# TankWaterLevelSensorV2_3.net
KiCad netlist of a schematic drawn in EAGLE
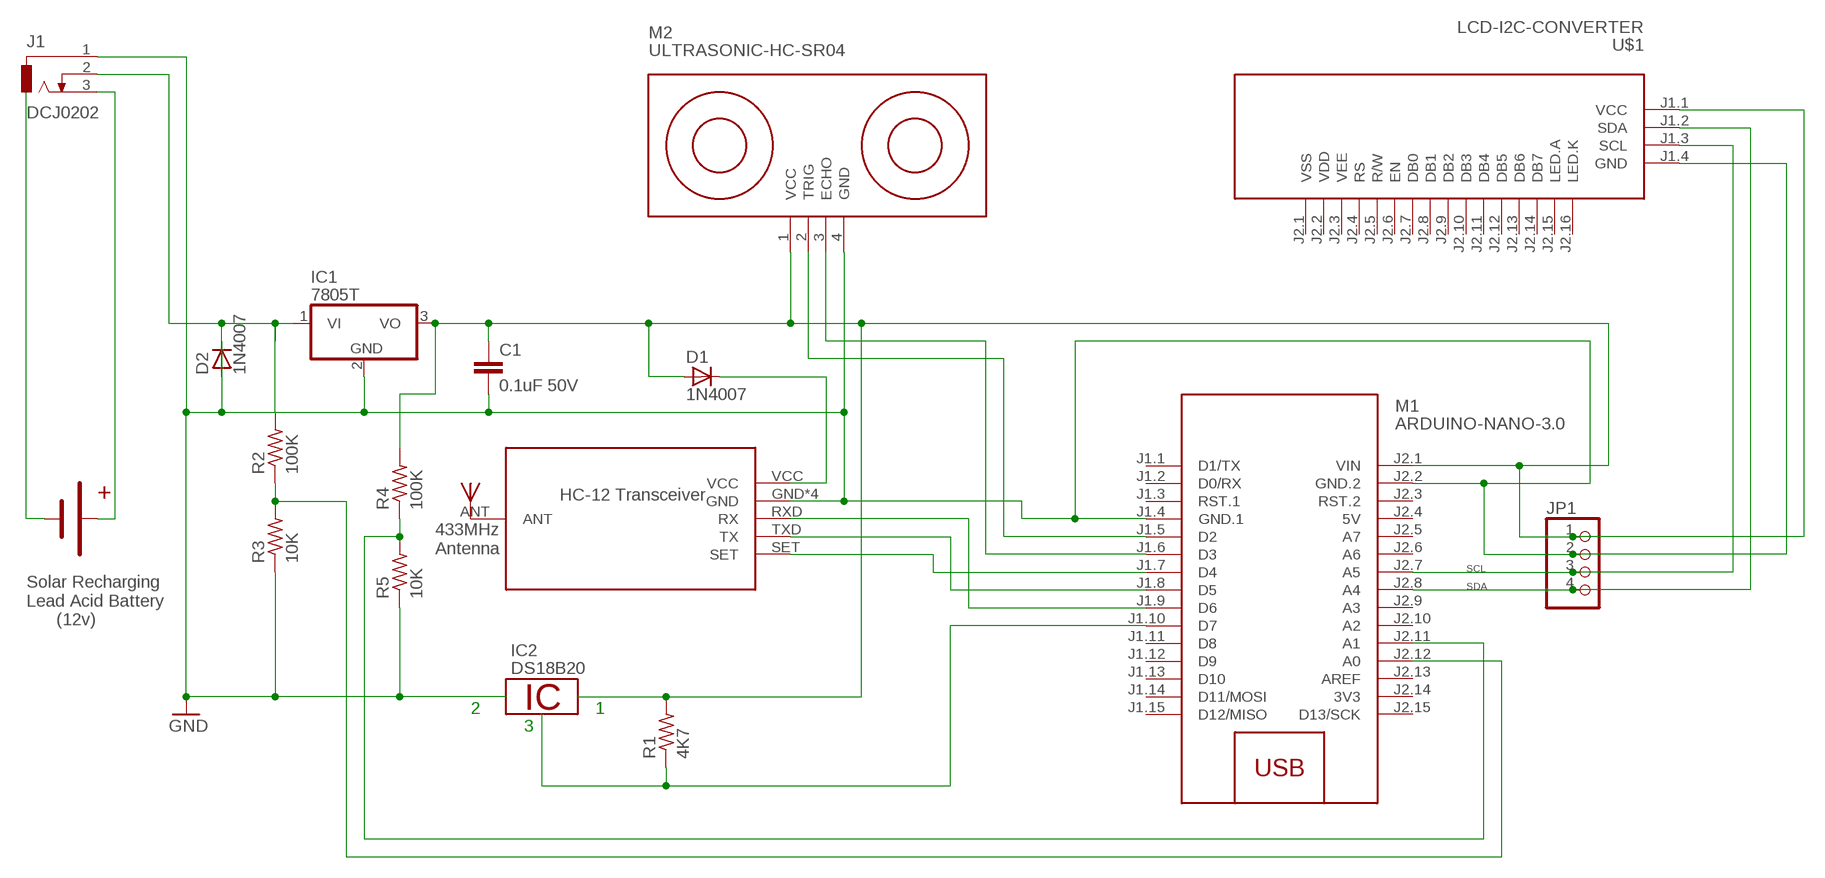
[diagram p0: schematic, sheet 1]

(export (version "E")
  (design (tool "Eeschema 10.0.6"))
  (components
    (comp (ref "433MHZ_ANT")
      (value "ANTENNA")
      (footprint "eagle-import:ANTENNA")
      (libsource (lib "eagle-import") (part "ANTENNA"))
    )
    (comp (ref "C1")
      (value "0.1uF 50V")
      (footprint "eagle-import:C5B2.5")
      (libsource (lib "eagle-import") (part "C5/2.5"))
    )
    (comp (ref "D1")
      (value "1N4007")
      (footprint "eagle-import:SMA")
      (libsource (lib "eagle-import") (part "1N4007"))
    )
    (comp (ref "D2")
      (value "1N4007")
      (footprint "eagle-import:SMA")
      (libsource (lib "eagle-import") (part "1N4007"))
    )
    (comp (ref "IC1")
      (value "7805T")
      (footprint "eagle-import:TO220H")
      (fields (field (name "SPICEPREFIX") "J"))
      (libsource (lib "eagle-import") (part "78T05"))
    )
    (comp (ref "IC2")
      (value "DS18B20")
      (footprint "eagle-import:TO92-")
      (libsource (lib "eagle-import") (part "DS18B20"))
    )
    (comp (ref "J1")
      (value "DCJ0202")
      (footprint "eagle-import:DCJ0202")
      (libsource (lib "eagle-import") (part "DCJ0202"))
    )
    (comp (ref "JP1")
      (value "PINHD-1X4/LONG")
      (footprint "eagle-import:1X04")
      (libsource (lib "eagle-import") (part "PINHD-1X4/LONG"))
    )
    (comp (ref "M1")
      (value "ARDUINO-NANO-3.0")
      (footprint "eagle-import:ARDUINO-NANO-3.0")
      (libsource (lib "eagle-import") (part "ARDUINO-NANO-3.0"))
    )
    (comp (ref "M2")
      (value "ULTRASONIC-HC-SR04")
      (footprint "eagle-import:ULTRASONIC-HC-SR04")
      (libsource (lib "eagle-import") (part "ULTRASONIC-HC-SR04"))
    )
    (comp (ref "M3")
      (value "HC-12_FOOTPRINT")
      (footprint "eagle-import:HC-12_FOOTPRINT")
      (libsource (lib "eagle-import") (part "HC-12_FOOTPRINT"))
    )
    (comp (ref "R1")
      (value "4K7")
      (footprint "eagle-import:0204V")
      (libsource (lib "eagle-import") (part "R-US_0204/2V"))
    )
    (comp (ref "R2")
      (value "100K")
      (footprint "eagle-import:0204V")
      (libsource (lib "eagle-import") (part "R-US_0204/2V"))
    )
    (comp (ref "R3")
      (value "10K")
      (footprint "eagle-import:0204V")
      (libsource (lib "eagle-import") (part "R-US_0204/2V"))
    )
    (comp (ref "R4")
      (value "100K")
      (footprint "eagle-import:0204V")
      (libsource (lib "eagle-import") (part "R-US_0204/2V"))
    )
    (comp (ref "R5")
      (value "10K")
      (footprint "eagle-import:0204V")
      (libsource (lib "eagle-import") (part "R-US_0204/2V"))
    )
    (comp (ref "SOLAR_BATTERY_12V")
      (value "12v")
      (footprint "eagle-import:BATTERYPAD")
      (libsource (lib "eagle-import") (part "BATTERYPAD"))
    )
    (comp (ref "U$1")
      (value "LCD-I2C-CONVERTER")
      (footprint "eagle-import:LCD-I2C-CONVERTER")
      (libsource (lib "eagle-import") (part "LCD-I2C-CONVERTER"))
    )
  )
  (nets
    (net (code "1") (name "/3V3") (class "Default")
      (node (ref "M1") (pin "J2.14") (pinfunction "3V3_J2.14") (pintype "power_in"))
    )
    (net (code "2") (name "/5V") (class "Default")
      (node (ref "M1") (pin "J2.4") (pinfunction "5V_J2.4") (pintype "power_in"))
    )
    (net (code "3") (name "GND") (class "Default")
      (node (ref "C1") (pin "2") (pinfunction "2_2") (pintype "passive"))
      (node (ref "D2") (pin "A") (pinfunction "A_A") (pintype "passive"))
      (node (ref "D2") (pin "K") (pinfunction "C_K") (pintype "passive"))
      (node (ref "IC1") (pin "1") (pinfunction "VI_1") (pintype "input"))
      (node (ref "IC1") (pin "2") (pinfunction "GND_2") (pintype "passive"))
      (node (ref "J1") (pin "1") (pinfunction "1_1") (pintype "passive"))
      (node (ref "J1") (pin "2") (pinfunction "2_2") (pintype "passive"))
      (node (ref "JP1") (pin "2") (pinfunction "2_2") (pintype "passive"))
      (node (ref "M1") (pin "J1.4") (pinfunction "GND.1_J1.4") (pintype "power_in"))
      (node (ref "M1") (pin "J2.2") (pinfunction "GND.2_J2.2") (pintype "power_in"))
      (node (ref "M2") (pin "4") (pinfunction "GND_4") (pintype "power_in"))
      (node (ref "M3") (pin "GND") (pinfunction "GND_GND") (pintype "bidirectional"))
      (node (ref "M3") (pin "GND1") (pinfunction "GND_GND1") (pintype "bidirectional"))
      (node (ref "M3") (pin "GND2") (pinfunction "GND_GND2") (pintype "bidirectional"))
      (node (ref "M3") (pin "MCHFIX") (pinfunction "GND_MCHFIX") (pintype "bidirectional"))
      (node (ref "R2") (pin "2") (pinfunction "2_2") (pintype "passive"))
      (node (ref "R3") (pin "1") (pinfunction "1_1") (pintype "passive"))
      (node (ref "R5") (pin "1") (pinfunction "1_1") (pintype "passive"))
      (node (ref "U$1") (pin "J1.4") (pinfunction "GND_J1.4") (pintype "power_in"))
    )
    (net (code "4") (name "Net-(433MHZ_ANT-PadANT)") (class "Default")
      (node (ref "433MHZ_ANT") (pin "ANT") (pinfunction "ANT_ANT") (pintype "bidirectional"))
      (node (ref "M3") (pin "ANT") (pinfunction "ANT_ANT") (pintype "bidirectional"))
    )
    (net (code "5") (name "Net-(D1-C)") (class "Default")
      (node (ref "D1") (pin "K") (pinfunction "C_K") (pintype "passive"))
      (node (ref "M3") (pin "VCC") (pinfunction "VCC_VCC") (pintype "bidirectional"))
    )
    (net (code "6") (name "Net-(IC1-VO)") (class "Default")
      (node (ref "C1") (pin "1") (pinfunction "1_1") (pintype "passive"))
      (node (ref "D1") (pin "A") (pinfunction "A_A") (pintype "passive"))
      (node (ref "IC1") (pin "3") (pinfunction "VO_3") (pintype "passive"))
      (node (ref "JP1") (pin "1") (pinfunction "1_1") (pintype "passive"))
      (node (ref "M1") (pin "J2.1") (pinfunction "VIN_J2.1") (pintype "power_in"))
      (node (ref "M2") (pin "1") (pinfunction "VCC_1") (pintype "power_in"))
      (node (ref "R1") (pin "2") (pinfunction "2_2") (pintype "passive"))
      (node (ref "R4") (pin "2") (pinfunction "2_2") (pintype "passive"))
      (node (ref "U$1") (pin "J1.1") (pinfunction "VCC_J1.1") (pintype "power_in"))
    )
    (net (code "7") (name "Net-(J1-Pad3)") (class "Default")
      (node (ref "J1") (pin "3") (pinfunction "3_3") (pintype "passive"))
      (node (ref "SOLAR_BATTERY_12V") (pin "+VE") (pinfunction "+VE_+VE") (pintype "power_in"))
    )
    (net (code "8") (name "Net-(M1-A0)") (class "Default")
      (node (ref "M1") (pin "J2.12") (pinfunction "A0_J2.12") (pintype "bidirectional"))
      (node (ref "R2") (pin "1") (pinfunction "1_1") (pintype "passive"))
      (node (ref "R3") (pin "2") (pinfunction "2_2") (pintype "passive"))
    )
    (net (code "9") (name "Net-(M1-A1)") (class "Default")
      (node (ref "M1") (pin "J2.11") (pinfunction "A1_J2.11") (pintype "bidirectional"))
      (node (ref "R4") (pin "1") (pinfunction "1_1") (pintype "passive"))
      (node (ref "R5") (pin "2") (pinfunction "2_2") (pintype "passive"))
    )
    (net (code "10") (name "Net-(M1-A4)") (class "Default")
      (node (ref "JP1") (pin "4") (pinfunction "4_4") (pintype "passive"))
      (node (ref "M1") (pin "J2.8") (pinfunction "A4_J2.8") (pintype "bidirectional"))
      (node (ref "U$1") (pin "J1.2") (pinfunction "SDA_J1.2") (pintype "bidirectional"))
    )
    (net (code "11") (name "Net-(M1-A5)") (class "Default")
      (node (ref "JP1") (pin "3") (pinfunction "3_3") (pintype "passive"))
      (node (ref "M1") (pin "J2.7") (pinfunction "A5_J2.7") (pintype "bidirectional"))
      (node (ref "U$1") (pin "J1.3") (pinfunction "SCL_J1.3") (pintype "bidirectional"))
    )
    (net (code "12") (name "Net-(M1-D2)") (class "Default")
      (node (ref "M1") (pin "J1.5") (pinfunction "D2_J1.5") (pintype "bidirectional"))
      (node (ref "M2") (pin "2") (pinfunction "TRIG_2") (pintype "input"))
    )
    (net (code "13") (name "Net-(M1-D3)") (class "Default")
      (node (ref "M1") (pin "J1.6") (pinfunction "D3_J1.6") (pintype "bidirectional"))
      (node (ref "M2") (pin "3") (pinfunction "ECHO_3") (pintype "output"))
    )
    (net (code "14") (name "Net-(M1-D4)") (class "Default")
      (node (ref "M1") (pin "J1.7") (pinfunction "D4_J1.7") (pintype "bidirectional"))
      (node (ref "M3") (pin "SET") (pinfunction "SET_SET") (pintype "bidirectional"))
    )
    (net (code "15") (name "Net-(M1-D5)") (class "Default")
      (node (ref "M1") (pin "J1.8") (pinfunction "D5_J1.8") (pintype "bidirectional"))
      (node (ref "M3") (pin "TXD") (pinfunction "TX_TXD") (pintype "bidirectional"))
    )
    (net (code "16") (name "Net-(M1-D6)") (class "Default")
      (node (ref "M1") (pin "J1.9") (pinfunction "D6_J1.9") (pintype "bidirectional"))
      (node (ref "M3") (pin "RXD") (pinfunction "RX_RXD") (pintype "bidirectional"))
    )
    (net (code "17") (name "Net-(M1-D7)") (class "Default")
      (node (ref "M1") (pin "J1.10") (pinfunction "D7_J1.10") (pintype "bidirectional"))
      (node (ref "R1") (pin "1") (pinfunction "1_1") (pintype "passive"))
    )
    (net (code "18") (name "unconnected-(M1-A2-PadJ2.10)") (class "Default")
      (node (ref "M1") (pin "J2.10") (pinfunction "A2_J2.10") (pintype "bidirectional"))
    )
    (net (code "19") (name "unconnected-(M1-A3-PadJ2.9)") (class "Default")
      (node (ref "M1") (pin "J2.9") (pinfunction "A3_J2.9") (pintype "bidirectional"))
    )
    (net (code "20") (name "unconnected-(M1-A6-PadJ2.6)") (class "Default")
      (node (ref "M1") (pin "J2.6") (pinfunction "A6_J2.6") (pintype "bidirectional"))
    )
    (net (code "21") (name "unconnected-(M1-A7-PadJ2.5)") (class "Default")
      (node (ref "M1") (pin "J2.5") (pinfunction "A7_J2.5") (pintype "bidirectional"))
    )
    (net (code "22") (name "unconnected-(M1-AREF-PadJ2.13)") (class "Default")
      (node (ref "M1") (pin "J2.13") (pinfunction "AREF_J2.13") (pintype "bidirectional"))
    )
    (net (code "23") (name "unconnected-(M1-D0{slash}RX-PadJ1.2)") (class "Default")
      (node (ref "M1") (pin "J1.2") (pinfunction "D0/RX_J1.2") (pintype "bidirectional"))
    )
    (net (code "24") (name "unconnected-(M1-D1{slash}TX-PadJ1.1)") (class "Default")
      (node (ref "M1") (pin "J1.1") (pinfunction "D1/TX_J1.1") (pintype "bidirectional"))
    )
    (net (code "25") (name "unconnected-(M1-D8-PadJ1.11)") (class "Default")
      (node (ref "M1") (pin "J1.11") (pinfunction "D8_J1.11") (pintype "bidirectional"))
    )
    (net (code "26") (name "unconnected-(M1-D9-PadJ1.12)") (class "Default")
      (node (ref "M1") (pin "J1.12") (pinfunction "D9_J1.12") (pintype "bidirectional"))
    )
    (net (code "27") (name "unconnected-(M1-D10-PadJ1.13)") (class "Default")
      (node (ref "M1") (pin "J1.13") (pinfunction "D10_J1.13") (pintype "bidirectional"))
    )
    (net (code "28") (name "unconnected-(M1-D11{slash}MOSI-PadJ1.14)") (class "Default")
      (node (ref "M1") (pin "J1.14") (pinfunction "D11/MOSI_J1.14") (pintype "bidirectional"))
    )
    (net (code "29") (name "unconnected-(M1-D12{slash}MISO-PadJ1.15)") (class "Default")
      (node (ref "M1") (pin "J1.15") (pinfunction "D12/MISO_J1.15") (pintype "bidirectional"))
    )
    (net (code "30") (name "unconnected-(M1-D13{slash}SCK-PadJ2.15)") (class "Default")
      (node (ref "M1") (pin "J2.15") (pinfunction "D13/SCK_J2.15") (pintype "bidirectional"))
    )
    (net (code "31") (name "unconnected-(M1-RST.1-PadJ1.3)") (class "Default")
      (node (ref "M1") (pin "J1.3") (pinfunction "RST.1_J1.3") (pintype "bidirectional"))
    )
    (net (code "32") (name "unconnected-(M1-RST.2-PadJ2.3)") (class "Default")
      (node (ref "M1") (pin "J2.3") (pinfunction "RST.2_J2.3") (pintype "bidirectional"))
    )
    (net (code "33") (name "unconnected-(SOLAR_BATTERY_12V-Pad-VE)") (class "Default")
      (node (ref "SOLAR_BATTERY_12V") (pin "-VE") (pinfunction "-VE_-VE") (pintype "power_in"))
    )
    (net (code "34") (name "unconnected-(U$1-DB0-PadJ2.7)") (class "Default")
      (node (ref "U$1") (pin "J2.7") (pinfunction "DB0_J2.7") (pintype "bidirectional"))
    )
    (net (code "35") (name "unconnected-(U$1-DB1-PadJ2.8)") (class "Default")
      (node (ref "U$1") (pin "J2.8") (pinfunction "DB1_J2.8") (pintype "bidirectional"))
    )
    (net (code "36") (name "unconnected-(U$1-DB2-PadJ2.9)") (class "Default")
      (node (ref "U$1") (pin "J2.9") (pinfunction "DB2_J2.9") (pintype "bidirectional"))
    )
    (net (code "37") (name "unconnected-(U$1-DB3-PadJ2.10)") (class "Default")
      (node (ref "U$1") (pin "J2.10") (pinfunction "DB3_J2.10") (pintype "bidirectional"))
    )
    (net (code "38") (name "unconnected-(U$1-DB4-PadJ2.11)") (class "Default")
      (node (ref "U$1") (pin "J2.11") (pinfunction "DB4_J2.11") (pintype "bidirectional"))
    )
    (net (code "39") (name "unconnected-(U$1-DB5-PadJ2.12)") (class "Default")
      (node (ref "U$1") (pin "J2.12") (pinfunction "DB5_J2.12") (pintype "bidirectional"))
    )
    (net (code "40") (name "unconnected-(U$1-DB6-PadJ2.13)") (class "Default")
      (node (ref "U$1") (pin "J2.13") (pinfunction "DB6_J2.13") (pintype "bidirectional"))
    )
    (net (code "41") (name "unconnected-(U$1-DB7-PadJ2.14)") (class "Default")
      (node (ref "U$1") (pin "J2.14") (pinfunction "DB7_J2.14") (pintype "bidirectional"))
    )
    (net (code "42") (name "unconnected-(U$1-EN-PadJ2.6)") (class "Default")
      (node (ref "U$1") (pin "J2.6") (pinfunction "EN_J2.6") (pintype "bidirectional"))
    )
    (net (code "43") (name "unconnected-(U$1-LED.A-PadJ2.15)") (class "Default")
      (node (ref "U$1") (pin "J2.15") (pinfunction "LED.A_J2.15") (pintype "bidirectional"))
    )
    (net (code "44") (name "unconnected-(U$1-LED.K-PadJ2.16)") (class "Default")
      (node (ref "U$1") (pin "J2.16") (pinfunction "LED.K_J2.16") (pintype "bidirectional"))
    )
    (net (code "45") (name "unconnected-(U$1-RS-PadJ2.4)") (class "Default")
      (node (ref "U$1") (pin "J2.4") (pinfunction "RS_J2.4") (pintype "bidirectional"))
    )
    (net (code "46") (name "unconnected-(U$1-R{slash}W-PadJ2.5)") (class "Default")
      (node (ref "U$1") (pin "J2.5") (pinfunction "R/W_J2.5") (pintype "bidirectional"))
    )
    (net (code "47") (name "unconnected-(U$1-VDD-PadJ2.2)") (class "Default")
      (node (ref "U$1") (pin "J2.2") (pinfunction "VDD_J2.2") (pintype "bidirectional"))
    )
    (net (code "48") (name "unconnected-(U$1-VEE-PadJ2.3)") (class "Default")
      (node (ref "U$1") (pin "J2.3") (pinfunction "VEE_J2.3") (pintype "bidirectional"))
    )
    (net (code "49") (name "unconnected-(U$1-VSS-PadJ2.1)") (class "Default")
      (node (ref "U$1") (pin "J2.1") (pinfunction "VSS_J2.1") (pintype "bidirectional"))
    )
  )
)
